# TCAN1146_PINOUT.net
KiCad netlist of a schematic drawn in Altium Designer
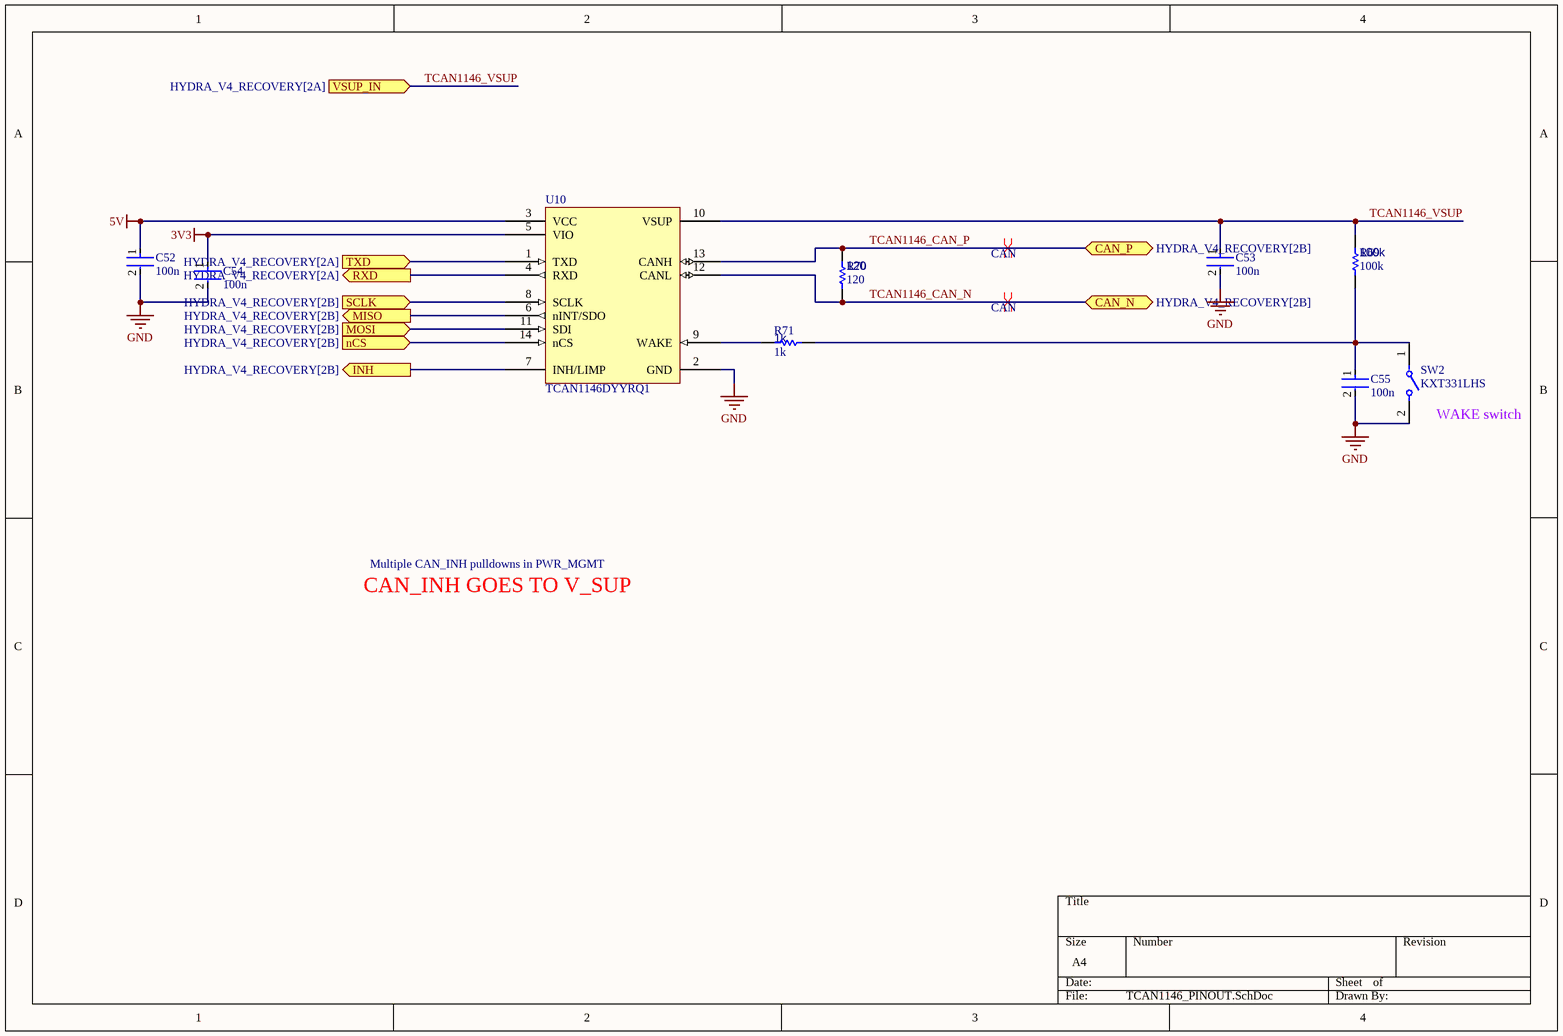
[diagram p0: TCAN1146_PINOUT.SchDoc]

(export (version "E")
  (design (tool "Eeschema 10.0.6"))
  (components
    (comp (ref "C52")
      (value "100n")
      (footprint "FP-0402-L_1_0_0_05-W_0_5-IPC_A")
      (description "LARGE PADS, 0402 CAP, CHANGE COMMENT TO MATCH REAL P/N")
      (libsource (lib "Space Concordia") (part "b4654b650e69147ec39a6b967a45e02"))
    )
    (comp (ref "C53")
      (value "100n")
      (footprint "FP-0402-L_1_0_0_05-W_0_5-IPC_A")
      (description "LARGE PADS, 0402 CAP, CHANGE COMMENT TO MATCH REAL P/N")
      (libsource (lib "Space Concordia") (part "b4654b650e69147ec39a6b967a45e02"))
    )
    (comp (ref "C54")
      (value "100n")
      (footprint "FP-0402-L_1_0_0_05-W_0_5-IPC_A")
      (description "LARGE PADS, 0402 CAP, CHANGE COMMENT TO MATCH REAL P/N")
      (libsource (lib "Space Concordia") (part "b4654b650e69147ec39a6b967a45e02"))
    )
    (comp (ref "C55")
      (value "100n")
      (footprint "FP-0402-L_1_0_0_05-W_0_5-IPC_A")
      (description "LARGE PADS, 0402 CAP, CHANGE COMMENT TO MATCH REAL P/N")
      (libsource (lib "Space Concordia") (part "b4654b650e69147ec39a6b967a45e02"))
    )
    (comp (ref "R69")
      (value "100k")
      (footprint "R0603B")
      (description "Resistor")
      (fields (field (name "ALTIUM_VALUE") "100k"))
      (libsource (lib "Space Concordia") (part "Resistor"))
    )
    (comp (ref "R70")
      (value "120")
      (footprint "R0603B")
      (description "Resistor")
      (fields (field (name "ALTIUM_VALUE") "120"))
      (libsource (lib "Space Concordia") (part "Resistor"))
    )
    (comp (ref "R71")
      (value "1k")
      (footprint "R0603B")
      (description "Resistor")
      (fields (field (name "ALTIUM_VALUE") "1k"))
      (libsource (lib "Space Concordia") (part "Resistor"))
    )
    (comp (ref "SW2")
      (value "KXT331LHS")
      (footprint "FP-KXT331LHS-MFG")
      (description "SWITCH TACTILE SPST-NO 0.02A 15V")
      (libsource (lib "Altium Content Vault") (part "bb27bde45df87f1f469753f287ef5ae"))
    )
    (comp (ref "U10")
      (value "TCAN1146DYYRQ1")
      (footprint "TCAN1146DYYRQ1-Footprint-1")
      (libsource (lib "Space Concordia") (part "CMP-015-00012-2"))
    )
  )
  (nets
    (net (code "1") (name "/INH") (class "Default")
      (node (ref "U10") (pin "7") (pinfunction "INH/LIMP_7") (pintype "passive"))
    )
    (net (code "2") (name "/MISO") (class "Default")
      (node (ref "U10") (pin "6") (pinfunction "nINT/SDO_6") (pintype "output"))
    )
    (net (code "3") (name "/MOSI") (class "Default")
      (node (ref "U10") (pin "11") (pinfunction "SDI_11") (pintype "input"))
    )
    (net (code "4") (name "/RXD") (class "Default")
      (node (ref "U10") (pin "4") (pinfunction "RXD_4") (pintype "output"))
    )
    (net (code "5") (name "/SCLK") (class "Default")
      (node (ref "U10") (pin "8") (pinfunction "SCLK_8") (pintype "input"))
    )
    (net (code "6") (name "/TCAN1146_CAN_N") (class "Default")
      (node (ref "R70") (pin "1") (pinfunction "1_1") (pintype "passive"))
      (node (ref "U10") (pin "12") (pinfunction "CANL_12") (pintype "bidirectional"))
    )
    (net (code "7") (name "/TCAN1146_CAN_P") (class "Default")
      (node (ref "R70") (pin "2") (pinfunction "2_2") (pintype "passive"))
      (node (ref "U10") (pin "13") (pinfunction "CANH_13") (pintype "bidirectional"))
    )
    (net (code "8") (name "/TCAN1146_VSUP") (class "Default")
      (node (ref "C53") (pin "1") (pinfunction "1_1") (pintype "passive"))
      (node (ref "R69") (pin "2") (pinfunction "2_2") (pintype "passive"))
      (node (ref "U10") (pin "10") (pinfunction "VSUP_10") (pintype "power_in"))
    )
    (net (code "9") (name "/TXD") (class "Default")
      (node (ref "U10") (pin "1") (pinfunction "TXD_1") (pintype "input"))
    )
    (net (code "10") (name "/nCS") (class "Default")
      (node (ref "U10") (pin "14") (pinfunction "nCS_14") (pintype "input"))
    )
    (net (code "11") (name "3V3") (class "Default")
      (node (ref "C54") (pin "1") (pinfunction "1_1") (pintype "passive"))
      (node (ref "U10") (pin "5") (pinfunction "VIO_5") (pintype "power_in"))
    )
    (net (code "12") (name "5V") (class "Default")
      (node (ref "C52") (pin "1") (pinfunction "1_1") (pintype "passive"))
      (node (ref "U10") (pin "3") (pinfunction "VCC_3") (pintype "power_in"))
    )
    (net (code "13") (name "GND") (class "Default")
      (node (ref "C52") (pin "2") (pinfunction "2_2") (pintype "passive"))
      (node (ref "C53") (pin "2") (pinfunction "2_2") (pintype "passive"))
      (node (ref "C54") (pin "2") (pinfunction "2_2") (pintype "passive"))
      (node (ref "C55") (pin "2") (pinfunction "2_2") (pintype "passive"))
      (node (ref "SW2") (pin "2") (pinfunction "2_2") (pintype "passive"))
      (node (ref "U10") (pin "2") (pinfunction "GND_2") (pintype "power_in"))
    )
    (net (code "14") (name "Net-(C55-Pad1)") (class "Default")
      (node (ref "C55") (pin "1") (pinfunction "1_1") (pintype "passive"))
      (node (ref "R69") (pin "1") (pinfunction "1_1") (pintype "passive"))
      (node (ref "R71") (pin "1") (pinfunction "1_1") (pintype "passive"))
      (node (ref "SW2") (pin "1") (pinfunction "1_1") (pintype "passive"))
    )
    (net (code "15") (name "Net-(U10-WAKE)") (class "Default")
      (node (ref "R71") (pin "2") (pinfunction "2_2") (pintype "passive"))
      (node (ref "U10") (pin "9") (pinfunction "WAKE_9") (pintype "input"))
    )
  )
)
